# dac.net
KiCad netlist of a schematic drawn in EAGLE
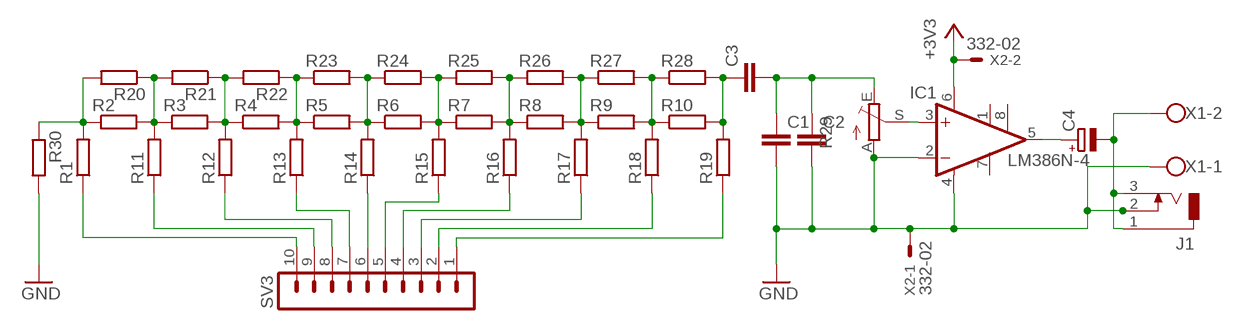
[diagram p0: schematic, sheet 1]

(export (version "E")
  (design (tool "Eeschema 10.0.6"))
  (components
    (comp (ref "C1")
      (value "C5/4.5")
      (footprint "eagle-import:C5B4.5")
      (libsource (lib "eagle-import") (part "C5/4.5"))
    )
    (comp (ref "C2")
      (value "C5/4.5")
      (footprint "eagle-import:C5B4.5")
      (libsource (lib "eagle-import") (part "C5/4.5"))
    )
    (comp (ref "C3")
      (value "C5/4.5")
      (footprint "eagle-import:C5B4.5")
      (libsource (lib "eagle-import") (part "C5/4.5"))
    )
    (comp (ref "C4")
      (value "CPOL-EUE5-6")
      (footprint "eagle-import:E5-6")
      (libsource (lib "eagle-import") (part "CPOL-EUE5-6"))
    )
    (comp (ref "IC1")
      (value "LM386N-4")
      (footprint "eagle-import:DIL08")
      (libsource (lib "eagle-import") (part "LM386?-N4"))
    )
    (comp (ref "J1")
      (value "DCJ0303")
      (footprint "eagle-import:DCJ0303")
      (libsource (lib "eagle-import") (part "DCJ0303"))
    )
    (comp (ref "R1")
      (value "R-EU_0309/10")
      (footprint "eagle-import:0309_10")
      (libsource (lib "eagle-import") (part "R-EU_0309/10"))
    )
    (comp (ref "R2")
      (value "R-EU_0309/10")
      (footprint "eagle-import:0309_10")
      (libsource (lib "eagle-import") (part "R-EU_0309/10"))
    )
    (comp (ref "R3")
      (value "R-EU_0309/10")
      (footprint "eagle-import:0309_10")
      (libsource (lib "eagle-import") (part "R-EU_0309/10"))
    )
    (comp (ref "R4")
      (value "R-EU_0309/10")
      (footprint "eagle-import:0309_10")
      (libsource (lib "eagle-import") (part "R-EU_0309/10"))
    )
    (comp (ref "R5")
      (value "R-EU_0309/10")
      (footprint "eagle-import:0309_10")
      (libsource (lib "eagle-import") (part "R-EU_0309/10"))
    )
    (comp (ref "R6")
      (value "R-EU_0309/10")
      (footprint "eagle-import:0309_10")
      (libsource (lib "eagle-import") (part "R-EU_0309/10"))
    )
    (comp (ref "R7")
      (value "R-EU_0309/10")
      (footprint "eagle-import:0309_10")
      (libsource (lib "eagle-import") (part "R-EU_0309/10"))
    )
    (comp (ref "R8")
      (value "R-EU_0309/10")
      (footprint "eagle-import:0309_10")
      (libsource (lib "eagle-import") (part "R-EU_0309/10"))
    )
    (comp (ref "R9")
      (value "R-EU_0309/10")
      (footprint "eagle-import:0309_10")
      (libsource (lib "eagle-import") (part "R-EU_0309/10"))
    )
    (comp (ref "R10")
      (value "R-EU_0309/10")
      (footprint "eagle-import:0309_10")
      (libsource (lib "eagle-import") (part "R-EU_0309/10"))
    )
    (comp (ref "R11")
      (value "R-EU_0309/10")
      (footprint "eagle-import:0309_10")
      (libsource (lib "eagle-import") (part "R-EU_0309/10"))
    )
    (comp (ref "R12")
      (value "R-EU_0309/10")
      (footprint "eagle-import:0309_10")
      (libsource (lib "eagle-import") (part "R-EU_0309/10"))
    )
    (comp (ref "R13")
      (value "R-EU_0309/10")
      (footprint "eagle-import:0309_10")
      (libsource (lib "eagle-import") (part "R-EU_0309/10"))
    )
    (comp (ref "R14")
      (value "R-EU_0309/10")
      (footprint "eagle-import:0309_10")
      (libsource (lib "eagle-import") (part "R-EU_0309/10"))
    )
    (comp (ref "R15")
      (value "R-EU_0309/10")
      (footprint "eagle-import:0309_10")
      (libsource (lib "eagle-import") (part "R-EU_0309/10"))
    )
    (comp (ref "R16")
      (value "R-EU_0309/10")
      (footprint "eagle-import:0309_10")
      (libsource (lib "eagle-import") (part "R-EU_0309/10"))
    )
    (comp (ref "R17")
      (value "R-EU_0309/10")
      (footprint "eagle-import:0309_10")
      (libsource (lib "eagle-import") (part "R-EU_0309/10"))
    )
    (comp (ref "R18")
      (value "R-EU_0309/10")
      (footprint "eagle-import:0309_10")
      (libsource (lib "eagle-import") (part "R-EU_0309/10"))
    )
    (comp (ref "R19")
      (value "R-EU_0309/10")
      (footprint "eagle-import:0309_10")
      (libsource (lib "eagle-import") (part "R-EU_0309/10"))
    )
    (comp (ref "R20")
      (value "R-EU_0309/10")
      (footprint "eagle-import:0309_10")
      (libsource (lib "eagle-import") (part "R-EU_0309/10"))
    )
    (comp (ref "R21")
      (value "R-EU_0309/10")
      (footprint "eagle-import:0309_10")
      (libsource (lib "eagle-import") (part "R-EU_0309/10"))
    )
    (comp (ref "R22")
      (value "R-EU_0309/10")
      (footprint "eagle-import:0309_10")
      (libsource (lib "eagle-import") (part "R-EU_0309/10"))
    )
    (comp (ref "R23")
      (value "R-EU_0309/10")
      (footprint "eagle-import:0309_10")
      (libsource (lib "eagle-import") (part "R-EU_0309/10"))
    )
    (comp (ref "R24")
      (value "R-EU_0309/10")
      (footprint "eagle-import:0309_10")
      (libsource (lib "eagle-import") (part "R-EU_0309/10"))
    )
    (comp (ref "R25")
      (value "R-EU_0309/10")
      (footprint "eagle-import:0309_10")
      (libsource (lib "eagle-import") (part "R-EU_0309/10"))
    )
    (comp (ref "R26")
      (value "R-EU_0309/10")
      (footprint "eagle-import:0309_10")
      (libsource (lib "eagle-import") (part "R-EU_0309/10"))
    )
    (comp (ref "R27")
      (value "R-EU_0309/10")
      (footprint "eagle-import:0309_10")
      (libsource (lib "eagle-import") (part "R-EU_0309/10"))
    )
    (comp (ref "R28")
      (value "R-EU_0309/10")
      (footprint "eagle-import:0309_10")
      (libsource (lib "eagle-import") (part "R-EU_0309/10"))
    )
    (comp (ref "R29")
      (value "TRIM_EU-CA9V")
      (footprint "eagle-import:CA9V")
      (libsource (lib "eagle-import") (part "TRIM_EU-CA9V"))
    )
    (comp (ref "R30")
      (value "R-EU_0309/10")
      (footprint "eagle-import:0309_10")
      (libsource (lib "eagle-import") (part "R-EU_0309/10"))
    )
    (comp (ref "SV3")
      (value "MA10-1W")
      (footprint "eagle-import:MA10-1W")
      (libsource (lib "eagle-import") (part "MA10-1W"))
    )
    (comp (ref "X1")
      (value "W237-102")
      (footprint "eagle-import:W237-102")
      (fields (field (name "MPN") "237-102"))
      (libsource (lib "eagle-import") (part "W237-102"))
    )
    (comp (ref "X2")
      (value "332-02")
      (footprint "eagle-import:332-02")
      (libsource (lib "eagle-import") (part "332-02"))
    )
  )
  (nets
    (net (code "1") (name "+3V3") (class "Default")
      (node (ref "IC1") (pin "6") (pinfunction "VS_6") (pintype "power_in"))
      (node (ref "X2") (pin "2") (pinfunction "S_2") (pintype "passive"))
    )
    (net (code "2") (name "GND") (class "Default")
      (node (ref "C1") (pin "2") (pinfunction "2_2") (pintype "passive"))
      (node (ref "C2") (pin "2") (pinfunction "2_2") (pintype "passive"))
      (node (ref "IC1") (pin "2") (pinfunction "-IN_2") (pintype "input"))
      (node (ref "IC1") (pin "4") (pinfunction "GND_4") (pintype "power_in"))
      (node (ref "J1") (pin "2") (pinfunction "2_2") (pintype "passive"))
      (node (ref "R29") (pin "A") (pinfunction "A_A") (pintype "passive"))
      (node (ref "R30") (pin "2") (pinfunction "2_2") (pintype "passive"))
      (node (ref "X1") (pin "1") (pinfunction "KL_1") (pintype "passive"))
      (node (ref "X2") (pin "1") (pinfunction "S_1") (pintype "passive"))
    )
    (net (code "3") (name "Net-(C1-Pad1)") (class "Default")
      (node (ref "C1") (pin "1") (pinfunction "1_1") (pintype "passive"))
      (node (ref "C2") (pin "1") (pinfunction "1_1") (pintype "passive"))
      (node (ref "C3") (pin "2") (pinfunction "2_2") (pintype "passive"))
      (node (ref "R29") (pin "E") (pinfunction "E_E") (pintype "passive"))
    )
    (net (code "4") (name "Net-(C3-Pad1)") (class "Default")
      (node (ref "C3") (pin "1") (pinfunction "1_1") (pintype "passive"))
      (node (ref "R10") (pin "2") (pinfunction "2_2") (pintype "passive"))
      (node (ref "R19") (pin "2") (pinfunction "2_2") (pintype "passive"))
      (node (ref "R28") (pin "2") (pinfunction "2_2") (pintype "passive"))
    )
    (net (code "5") (name "Net-(IC1-+IN)") (class "Default")
      (node (ref "IC1") (pin "3") (pinfunction "+IN_3") (pintype "input"))
      (node (ref "R29") (pin "S") (pinfunction "S_S") (pintype "passive"))
    )
    (net (code "6") (name "Net-(IC1-OUT)") (class "Default")
      (node (ref "C4") (pin "+") (pinfunction "+_+") (pintype "passive"))
      (node (ref "IC1") (pin "5") (pinfunction "OUT_5") (pintype "output"))
    )
    (net (code "7") (name "Net-(R1-Pad1)") (class "Default")
      (node (ref "R1") (pin "1") (pinfunction "1_1") (pintype "passive"))
      (node (ref "SV3") (pin "10") (pinfunction "10_10") (pintype "passive"))
    )
    (net (code "8") (name "Net-(R1-Pad2)") (class "Default")
      (node (ref "R1") (pin "2") (pinfunction "2_2") (pintype "passive"))
      (node (ref "R2") (pin "1") (pinfunction "1_1") (pintype "passive"))
      (node (ref "R20") (pin "2") (pinfunction "2_2") (pintype "passive"))
      (node (ref "R30") (pin "1") (pinfunction "1_1") (pintype "passive"))
    )
    (net (code "9") (name "Net-(R10-Pad1)") (class "Default")
      (node (ref "R10") (pin "1") (pinfunction "1_1") (pintype "passive"))
      (node (ref "R18") (pin "2") (pinfunction "2_2") (pintype "passive"))
      (node (ref "R27") (pin "2") (pinfunction "2_2") (pintype "passive"))
      (node (ref "R28") (pin "1") (pinfunction "1_1") (pintype "passive"))
      (node (ref "R9") (pin "2") (pinfunction "2_2") (pintype "passive"))
    )
    (net (code "10") (name "Net-(R11-Pad1)") (class "Default")
      (node (ref "R11") (pin "1") (pinfunction "1_1") (pintype "passive"))
      (node (ref "SV3") (pin "9") (pinfunction "9_9") (pintype "passive"))
    )
    (net (code "11") (name "Net-(R11-Pad2)") (class "Default")
      (node (ref "R11") (pin "2") (pinfunction "2_2") (pintype "passive"))
      (node (ref "R2") (pin "2") (pinfunction "2_2") (pintype "passive"))
      (node (ref "R20") (pin "1") (pinfunction "1_1") (pintype "passive"))
      (node (ref "R21") (pin "2") (pinfunction "2_2") (pintype "passive"))
      (node (ref "R3") (pin "1") (pinfunction "1_1") (pintype "passive"))
    )
    (net (code "12") (name "Net-(R12-Pad1)") (class "Default")
      (node (ref "R12") (pin "1") (pinfunction "1_1") (pintype "passive"))
      (node (ref "SV3") (pin "8") (pinfunction "8_8") (pintype "passive"))
    )
    (net (code "13") (name "Net-(R12-Pad2)") (class "Default")
      (node (ref "R12") (pin "2") (pinfunction "2_2") (pintype "passive"))
      (node (ref "R21") (pin "1") (pinfunction "1_1") (pintype "passive"))
      (node (ref "R22") (pin "2") (pinfunction "2_2") (pintype "passive"))
      (node (ref "R3") (pin "2") (pinfunction "2_2") (pintype "passive"))
      (node (ref "R4") (pin "1") (pinfunction "1_1") (pintype "passive"))
    )
    (net (code "14") (name "Net-(R13-Pad1)") (class "Default")
      (node (ref "R13") (pin "1") (pinfunction "1_1") (pintype "passive"))
      (node (ref "SV3") (pin "7") (pinfunction "7_7") (pintype "passive"))
    )
    (net (code "15") (name "Net-(R13-Pad2)") (class "Default")
      (node (ref "R13") (pin "2") (pinfunction "2_2") (pintype "passive"))
      (node (ref "R22") (pin "1") (pinfunction "1_1") (pintype "passive"))
      (node (ref "R23") (pin "1") (pinfunction "1_1") (pintype "passive"))
      (node (ref "R4") (pin "2") (pinfunction "2_2") (pintype "passive"))
      (node (ref "R5") (pin "1") (pinfunction "1_1") (pintype "passive"))
    )
    (net (code "16") (name "Net-(R14-Pad1)") (class "Default")
      (node (ref "R14") (pin "1") (pinfunction "1_1") (pintype "passive"))
      (node (ref "SV3") (pin "6") (pinfunction "6_6") (pintype "passive"))
    )
    (net (code "17") (name "Net-(R14-Pad2)") (class "Default")
      (node (ref "R14") (pin "2") (pinfunction "2_2") (pintype "passive"))
      (node (ref "R23") (pin "2") (pinfunction "2_2") (pintype "passive"))
      (node (ref "R24") (pin "1") (pinfunction "1_1") (pintype "passive"))
      (node (ref "R5") (pin "2") (pinfunction "2_2") (pintype "passive"))
      (node (ref "R6") (pin "1") (pinfunction "1_1") (pintype "passive"))
    )
    (net (code "18") (name "Net-(R15-Pad1)") (class "Default")
      (node (ref "R15") (pin "1") (pinfunction "1_1") (pintype "passive"))
      (node (ref "SV3") (pin "5") (pinfunction "5_5") (pintype "passive"))
    )
    (net (code "19") (name "Net-(R15-Pad2)") (class "Default")
      (node (ref "R15") (pin "2") (pinfunction "2_2") (pintype "passive"))
      (node (ref "R24") (pin "2") (pinfunction "2_2") (pintype "passive"))
      (node (ref "R25") (pin "1") (pinfunction "1_1") (pintype "passive"))
      (node (ref "R6") (pin "2") (pinfunction "2_2") (pintype "passive"))
      (node (ref "R7") (pin "1") (pinfunction "1_1") (pintype "passive"))
    )
    (net (code "20") (name "Net-(R16-Pad1)") (class "Default")
      (node (ref "R16") (pin "1") (pinfunction "1_1") (pintype "passive"))
      (node (ref "SV3") (pin "4") (pinfunction "4_4") (pintype "passive"))
    )
    (net (code "21") (name "Net-(R16-Pad2)") (class "Default")
      (node (ref "R16") (pin "2") (pinfunction "2_2") (pintype "passive"))
      (node (ref "R25") (pin "2") (pinfunction "2_2") (pintype "passive"))
      (node (ref "R26") (pin "1") (pinfunction "1_1") (pintype "passive"))
      (node (ref "R7") (pin "2") (pinfunction "2_2") (pintype "passive"))
      (node (ref "R8") (pin "1") (pinfunction "1_1") (pintype "passive"))
    )
    (net (code "22") (name "Net-(R17-Pad1)") (class "Default")
      (node (ref "R17") (pin "1") (pinfunction "1_1") (pintype "passive"))
      (node (ref "SV3") (pin "3") (pinfunction "3_3") (pintype "passive"))
    )
    (net (code "23") (name "Net-(R17-Pad2)") (class "Default")
      (node (ref "R17") (pin "2") (pinfunction "2_2") (pintype "passive"))
      (node (ref "R26") (pin "2") (pinfunction "2_2") (pintype "passive"))
      (node (ref "R27") (pin "1") (pinfunction "1_1") (pintype "passive"))
      (node (ref "R8") (pin "2") (pinfunction "2_2") (pintype "passive"))
      (node (ref "R9") (pin "1") (pinfunction "1_1") (pintype "passive"))
    )
    (net (code "24") (name "Net-(R18-Pad1)") (class "Default")
      (node (ref "R18") (pin "1") (pinfunction "1_1") (pintype "passive"))
      (node (ref "SV3") (pin "2") (pinfunction "2_2") (pintype "passive"))
    )
    (net (code "25") (name "Net-(R19-Pad1)") (class "Default")
      (node (ref "R19") (pin "1") (pinfunction "1_1") (pintype "passive"))
      (node (ref "SV3") (pin "1") (pinfunction "1_1") (pintype "passive"))
    )
    (net (code "26") (name "Net-(X1B-KL)") (class "Default")
      (node (ref "C4") (pin "-") (pinfunction "-_-") (pintype "passive"))
      (node (ref "J1") (pin "1") (pinfunction "1_1") (pintype "passive"))
      (node (ref "J1") (pin "3") (pinfunction "3_3") (pintype "passive"))
      (node (ref "X1") (pin "2") (pinfunction "KL_2") (pintype "passive"))
    )
    (net (code "27") (name "unconnected-(IC1-BYPASS-Pad7)") (class "Default")
      (node (ref "IC1") (pin "7") (pinfunction "BYPASS_7") (pintype "passive"))
    )
    (net (code "28") (name "unconnected-(IC1-GAIN-Pad1)") (class "Default")
      (node (ref "IC1") (pin "1") (pinfunction "GAIN_1") (pintype "passive"))
    )
    (net (code "29") (name "unconnected-(IC1-GAIN-Pad8)") (class "Default")
      (node (ref "IC1") (pin "8") (pinfunction "GAIN_8") (pintype "passive"))
    )
  )
)
